# USB.net
KiCad netlist of a schematic drawn in Altium Designer
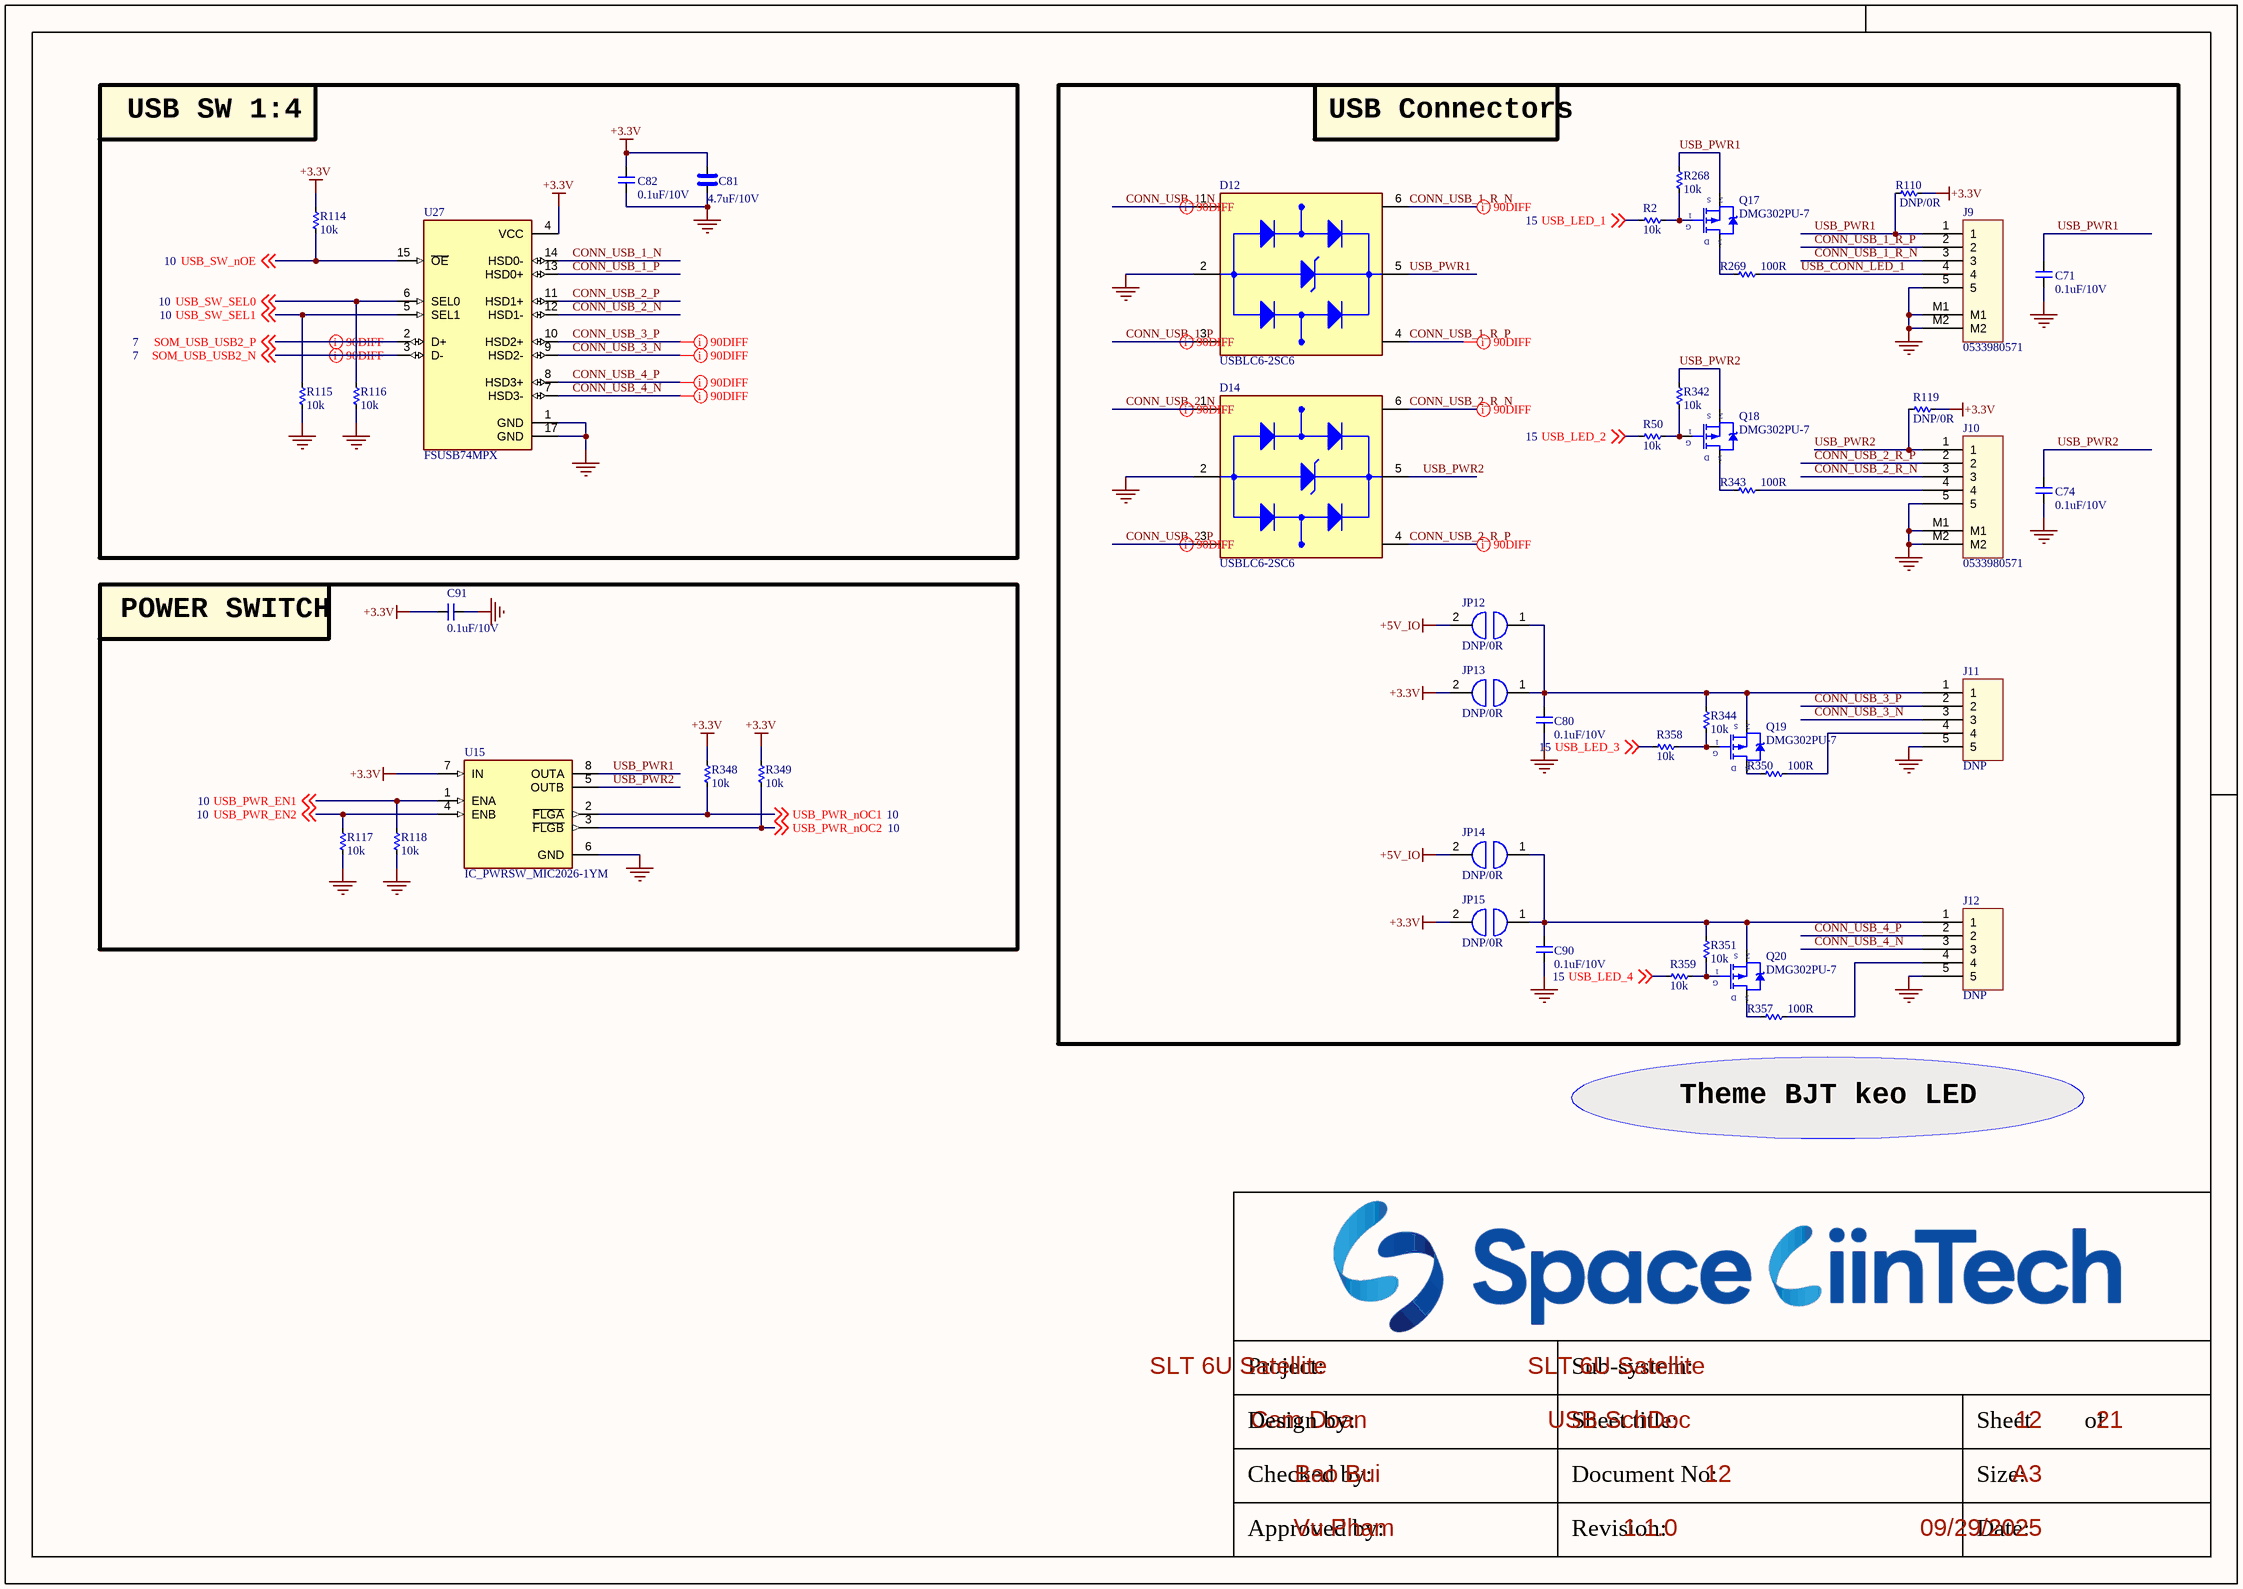
[diagram p0: USB.SchDoc]

(export (version "E")
  (design (tool "Eeschema 10.0.6"))
  (components
    (comp (ref "C71")
      (value "0.1uF/10V")
      (footprint "CAP_C_1005X60")
      (description "CAP CHIP")
      (libsource (lib "LABLIB") (part "_CAP_C_2"))
    )
    (comp (ref "C74")
      (value "0.1uF/10V")
      (footprint "CAP_C_1005X60")
      (description "CAP CHIP")
      (libsource (lib "LABLIB") (part "_CAP_C_2"))
    )
    (comp (ref "C80")
      (value "0.1uF/10V")
      (footprint "CAP_C_1005X60")
      (description "CAP CHIP")
      (libsource (lib "LABLIB") (part "_CAP_C_2"))
    )
    (comp (ref "C81")
      (value "4.7uF/10V")
      (footprint "CAP_C_1608X80")
      (description "CAP CHIP High Value")
      (libsource (lib "LABLIB") (part "_CAP_C_High_2"))
    )
    (comp (ref "C82")
      (value "0.1uF/10V")
      (footprint "CAP_C_1005X60")
      (description "CAP CHIP")
      (libsource (lib "LABLIB") (part "_CAP_C_2"))
    )
    (comp (ref "C90")
      (value "0.1uF/10V")
      (footprint "CAP_C_1005X60")
      (description "CAP CHIP")
      (libsource (lib "LABLIB") (part "_CAP_C_2"))
    )
    (comp (ref "C91")
      (value "0.1uF/10V")
      (footprint "CAP_C_1005X60")
      (description "CAP CHIP")
      (libsource (lib "LABLIB") (part "_CAP_C_2"))
    )
    (comp (ref "D12")
      (value "USBLC6-2SC6")
      (footprint "SOT95P280X145-6N")
      (description "17V Clamp 5A (8/20Âµs) Ipp Tvs Diode Surface Mount SOT-23-6")
      (fields (field (name "MF") "STMicroelectronics"))
      (libsource (lib "USBLC6-2SC6") (part "USBLC6-2SC6"))
    )
    (comp (ref "D14")
      (value "USBLC6-2SC6")
      (footprint "SOT95P280X145-6N")
      (description "17V Clamp 5A (8/20Âµs) Ipp Tvs Diode Surface Mount SOT-23-6")
      (fields (field (name "MF") "STMicroelectronics"))
      (libsource (lib "USBLC6-2SC6") (part "USBLC6-2SC6"))
    )
    (comp (ref "J9")
      (value "0533980571")
      (footprint "MOLEX_0533980571")
      (libsource (lib "LABLIB") (part "Header 5x1_2M"))
    )
    (comp (ref "J10")
      (value "0533980571")
      (footprint "MOLEX_0533980571")
      (libsource (lib "LABLIB") (part "Header 5x1_2M"))
    )
    (comp (ref "J11") (value "DNP") (footprint "SMD_5_PIN") (libsource (lib "LABLIB") (part "Header 5x1")))
    (comp (ref "J12") (value "DNP") (footprint "SMD_5_PIN") (libsource (lib "LABLIB") (part "Header 5x1")))
    (comp (ref "JP12")
      (value "DNP/0R")
      (footprint "RES_C_1608X60")
      (libsource (lib "EXP_V1") (part "JUMPER"))
    )
    (comp (ref "JP13")
      (value "DNP/0R")
      (footprint "RES_C_1608X60")
      (libsource (lib "EXP_V1") (part "JUMPER"))
    )
    (comp (ref "JP14")
      (value "DNP/0R")
      (footprint "RES_C_1608X60")
      (libsource (lib "EXP_V1") (part "JUMPER"))
    )
    (comp (ref "JP15")
      (value "DNP/0R")
      (footprint "RES_C_1608X60")
      (libsource (lib "EXP_V1") (part "JUMPER"))
    )
    (comp (ref "Q17")
      (value "DMG302PU-7")
      (footprint "SOT95P240X120-3N")
      (libsource (lib "LABLIB") (part "MOSFET_P_GSD"))
    )
    (comp (ref "Q18")
      (value "DMG302PU-7")
      (footprint "SOT95P240X120-3N")
      (libsource (lib "LABLIB") (part "MOSFET_P_GSD"))
    )
    (comp (ref "Q19")
      (value "DMG302PU-7")
      (footprint "SOT95P240X120-3N")
      (libsource (lib "LABLIB") (part "MOSFET_P_GSD"))
    )
    (comp (ref "Q20")
      (value "DMG302PU-7")
      (footprint "SOT95P240X120-3N")
      (libsource (lib "LABLIB") (part "MOSFET_P_GSD"))
    )
    (comp (ref "R2")
      (value "10k")
      (footprint "RES_C_1005X40")
      (description "RES")
      (libsource (lib "LABLIB") (part "_RES_B_2"))
    )
    (comp (ref "R50")
      (value "10k")
      (footprint "RES_C_1005X40")
      (description "RES")
      (libsource (lib "LABLIB") (part "_RES_B_2"))
    )
    (comp (ref "R110")
      (value "DNP/0R")
      (footprint "RES_C_1005X40")
      (description "RES")
      (libsource (lib "LABLIB") (part "_RES_B_2"))
    )
    (comp (ref "R114")
      (value "10k")
      (footprint "RES_C_1005X40")
      (description "RES")
      (libsource (lib "LABLIB") (part "_RES_B_2"))
    )
    (comp (ref "R115")
      (value "10k")
      (footprint "RES_C_1005X40")
      (description "RES")
      (libsource (lib "LABLIB") (part "_RES_B_2"))
    )
    (comp (ref "R116")
      (value "10k")
      (footprint "RES_C_1005X40")
      (description "RES")
      (libsource (lib "LABLIB") (part "_RES_B_2"))
    )
    (comp (ref "R117")
      (value "10k")
      (footprint "RES_C_1005X40")
      (description "RES")
      (libsource (lib "LABLIB") (part "_RES_B_2"))
    )
    (comp (ref "R118")
      (value "10k")
      (footprint "RES_C_1005X40")
      (description "RES")
      (libsource (lib "LABLIB") (part "_RES_B_2"))
    )
    (comp (ref "R119")
      (value "DNP/0R")
      (footprint "RES_C_1005X40")
      (description "RES")
      (libsource (lib "LABLIB") (part "_RES_B_2"))
    )
    (comp (ref "R268")
      (value "10k")
      (footprint "RES_C_1005X40")
      (description "RES")
      (libsource (lib "LABLIB") (part "_RES_B_2"))
    )
    (comp (ref "R269")
      (value "100R")
      (footprint "RES_C_1005X40")
      (description "RES")
      (libsource (lib "LABLIB") (part "_RES_B_2"))
    )
    (comp (ref "R342")
      (value "10k")
      (footprint "RES_C_1005X40")
      (description "RES")
      (libsource (lib "LABLIB") (part "_RES_B_2"))
    )
    (comp (ref "R343")
      (value "100R")
      (footprint "RES_C_1005X40")
      (description "RES")
      (libsource (lib "LABLIB") (part "_RES_B_2"))
    )
    (comp (ref "R344")
      (value "10k")
      (footprint "RES_C_1005X40")
      (description "RES")
      (libsource (lib "LABLIB") (part "_RES_B_2"))
    )
    (comp (ref "R348")
      (value "10k")
      (footprint "RES_C_1005X40")
      (description "RES")
      (libsource (lib "LABLIB") (part "_RES_B_2"))
    )
    (comp (ref "R349")
      (value "10k")
      (footprint "RES_C_1005X40")
      (description "RES")
      (libsource (lib "LABLIB") (part "_RES_B_2"))
    )
    (comp (ref "R350")
      (value "100R")
      (footprint "RES_C_1005X40")
      (description "RES")
      (libsource (lib "LABLIB") (part "_RES_B_2"))
    )
    (comp (ref "R351")
      (value "10k")
      (footprint "RES_C_1005X40")
      (description "RES")
      (libsource (lib "LABLIB") (part "_RES_B_2"))
    )
    (comp (ref "R357")
      (value "100R")
      (footprint "RES_C_1005X40")
      (description "RES")
      (libsource (lib "LABLIB") (part "_RES_B_2"))
    )
    (comp (ref "R358")
      (value "10k")
      (footprint "RES_C_1005X40")
      (description "RES")
      (libsource (lib "LABLIB") (part "_RES_B_2"))
    )
    (comp (ref "R359")
      (value "10k")
      (footprint "RES_C_1005X40")
      (description "RES")
      (libsource (lib "LABLIB") (part "_RES_B_2"))
    )
    (comp (ref "U15")
      (value "IC_PWRSW_MIC2026-1YM")
      (footprint "SOIC127P602X173-8N")
      (description "Power Switch/Driver 1:2 N-Channel 1.25A 8-SOIC")
      (fields (field (name "MF") "Microchip") (field (name "MP") "MIC2026-1YM"))
      (libsource (lib "LABLIB") (part "IC_PWRSW_MIC2026-1YM"))
    )
    (comp (ref "U27")
      (value "FSUSB74MPX")
      (footprint "QFN50P300X300X80-17N")
      (description "USB Switch IC 1 Channel 16-MLP (3x3)")
      (fields (field (name "MF") "ON Semiconductor"))
      (libsource (lib "LABLIB") (part "IC_USB_SW_FSUSB74MPX"))
    )
  )
  (nets
    (net (code "1") (name "+3.3V") (class "Default")
      (node (ref "C81") (pin "2") (pinfunction "2_2") (pintype "passive"))
      (node (ref "C82") (pin "2") (pinfunction "2_2") (pintype "passive"))
      (node (ref "C91") (pin "2") (pinfunction "2_2") (pintype "passive"))
      (node (ref "JP13") (pin "2") (pinfunction "2_2") (pintype "passive"))
      (node (ref "JP15") (pin "2") (pinfunction "2_2") (pintype "passive"))
      (node (ref "R110") (pin "1") (pinfunction "1_1") (pintype "passive"))
      (node (ref "R114") (pin "1") (pinfunction "1_1") (pintype "passive"))
      (node (ref "R119") (pin "1") (pinfunction "1_1") (pintype "passive"))
      (node (ref "R348") (pin "1") (pinfunction "1_1") (pintype "passive"))
      (node (ref "R349") (pin "1") (pinfunction "1_1") (pintype "passive"))
      (node (ref "U15") (pin "7") (pinfunction "IN_7") (pintype "input"))
      (node (ref "U27") (pin "4") (pinfunction "VCC_4") (pintype "power_in"))
    )
    (net (code "2") (name "+5V_IO") (class "Default")
      (node (ref "JP12") (pin "2") (pinfunction "2_2") (pintype "passive"))
      (node (ref "JP14") (pin "2") (pinfunction "2_2") (pintype "passive"))
    )
    (net (code "3") (name "/CONN_USB_1_N") (class "Default")
      (node (ref "D12") (pin "1") (pinfunction "I/O1_IN_1") (pintype "passive"))
      (node (ref "U27") (pin "14") (pinfunction "HSD0-_14") (pintype "bidirectional"))
    )
    (net (code "4") (name "/CONN_USB_1_P") (class "Default")
      (node (ref "D12") (pin "3") (pinfunction "I/O2_IN_3") (pintype "passive"))
      (node (ref "U27") (pin "13") (pinfunction "HSD0+_13") (pintype "bidirectional"))
    )
    (net (code "5") (name "/CONN_USB_1_R_N") (class "Default")
      (node (ref "D12") (pin "6") (pinfunction "I/O1_OUT_6") (pintype "passive"))
      (node (ref "J9") (pin "3") (pinfunction "3_3") (pintype "passive"))
    )
    (net (code "6") (name "/CONN_USB_1_R_P") (class "Default")
      (node (ref "D12") (pin "4") (pinfunction "I/O2_OUT_4") (pintype "passive"))
      (node (ref "J9") (pin "2") (pinfunction "2_2") (pintype "passive"))
    )
    (net (code "7") (name "/CONN_USB_2_N") (class "Default")
      (node (ref "D14") (pin "1") (pinfunction "I/O1_IN_1") (pintype "passive"))
      (node (ref "U27") (pin "12") (pinfunction "HSD1-_12") (pintype "bidirectional"))
    )
    (net (code "8") (name "/CONN_USB_2_P") (class "Default")
      (node (ref "D14") (pin "3") (pinfunction "I/O2_IN_3") (pintype "passive"))
      (node (ref "U27") (pin "11") (pinfunction "HSD1+_11") (pintype "bidirectional"))
    )
    (net (code "9") (name "/CONN_USB_2_R_N") (class "Default")
      (node (ref "D14") (pin "6") (pinfunction "I/O1_OUT_6") (pintype "passive"))
      (node (ref "J10") (pin "3") (pinfunction "3_3") (pintype "passive"))
    )
    (net (code "10") (name "/CONN_USB_2_R_P") (class "Default")
      (node (ref "D14") (pin "4") (pinfunction "I/O2_OUT_4") (pintype "passive"))
      (node (ref "J10") (pin "2") (pinfunction "2_2") (pintype "passive"))
    )
    (net (code "11") (name "/CONN_USB_3_N") (class "Default")
      (node (ref "J11") (pin "3") (pinfunction "3_3") (pintype "passive"))
      (node (ref "U27") (pin "9") (pinfunction "HSD2-_9") (pintype "bidirectional"))
    )
    (net (code "12") (name "/CONN_USB_3_P") (class "Default")
      (node (ref "J11") (pin "2") (pinfunction "2_2") (pintype "passive"))
      (node (ref "U27") (pin "10") (pinfunction "HSD2+_10") (pintype "bidirectional"))
    )
    (net (code "13") (name "/CONN_USB_4_N") (class "Default")
      (node (ref "J12") (pin "3") (pinfunction "3_3") (pintype "passive"))
      (node (ref "U27") (pin "7") (pinfunction "HSD3-_7") (pintype "bidirectional"))
    )
    (net (code "14") (name "/CONN_USB_4_P") (class "Default")
      (node (ref "J12") (pin "2") (pinfunction "2_2") (pintype "passive"))
      (node (ref "U27") (pin "8") (pinfunction "HSD3+_8") (pintype "bidirectional"))
    )
    (net (code "15") (name "/USB_CONN_LED_1") (class "Default")
      (node (ref "J9") (pin "4") (pinfunction "4_4") (pintype "passive"))
      (node (ref "R269") (pin "2") (pinfunction "2_2") (pintype "passive"))
    )
    (net (code "16") (name "/USB_PWR1") (class "Default")
      (node (ref "C71") (pin "2") (pinfunction "2_2") (pintype "passive"))
      (node (ref "D12") (pin "5") (pinfunction "VBUS_5") (pintype "power_in"))
      (node (ref "J9") (pin "1") (pinfunction "1_1") (pintype "passive"))
      (node (ref "Q17") (pin "2") (pinfunction "S_2") (pintype "passive"))
      (node (ref "R110") (pin "2") (pinfunction "2_2") (pintype "passive"))
      (node (ref "R268") (pin "1") (pinfunction "1_1") (pintype "passive"))
      (node (ref "U15") (pin "8") (pinfunction "OUTA_8") (pintype "passive"))
    )
    (net (code "17") (name "/USB_PWR2") (class "Default")
      (node (ref "C74") (pin "2") (pinfunction "2_2") (pintype "passive"))
      (node (ref "D14") (pin "5") (pinfunction "VBUS_5") (pintype "power_in"))
      (node (ref "J10") (pin "1") (pinfunction "1_1") (pintype "passive"))
      (node (ref "Q18") (pin "2") (pinfunction "S_2") (pintype "passive"))
      (node (ref "R119") (pin "2") (pinfunction "2_2") (pintype "passive"))
      (node (ref "R342") (pin "1") (pinfunction "1_1") (pintype "passive"))
      (node (ref "U15") (pin "5") (pinfunction "OUTB_5") (pintype "passive"))
    )
    (net (code "18") (name "GND") (class "Default")
      (node (ref "C71") (pin "1") (pinfunction "1_1") (pintype "passive"))
      (node (ref "C74") (pin "1") (pinfunction "1_1") (pintype "passive"))
      (node (ref "C80") (pin "1") (pinfunction "1_1") (pintype "passive"))
      (node (ref "C81") (pin "1") (pinfunction "1_1") (pintype "passive"))
      (node (ref "C82") (pin "1") (pinfunction "1_1") (pintype "passive"))
      (node (ref "C90") (pin "1") (pinfunction "1_1") (pintype "passive"))
      (node (ref "C91") (pin "1") (pinfunction "1_1") (pintype "passive"))
      (node (ref "D12") (pin "2") (pinfunction "GND_2") (pintype "power_in"))
      (node (ref "D14") (pin "2") (pinfunction "GND_2") (pintype "power_in"))
      (node (ref "J10") (pin "5") (pinfunction "5_5") (pintype "passive"))
      (node (ref "J10") (pin "M1") (pinfunction "M1_M1") (pintype "passive"))
      (node (ref "J10") (pin "M2") (pinfunction "M2_M2") (pintype "passive"))
      (node (ref "J11") (pin "5") (pinfunction "5_5") (pintype "passive"))
      (node (ref "J12") (pin "5") (pinfunction "5_5") (pintype "passive"))
      (node (ref "J9") (pin "5") (pinfunction "5_5") (pintype "passive"))
      (node (ref "J9") (pin "M1") (pinfunction "M1_M1") (pintype "passive"))
      (node (ref "J9") (pin "M2") (pinfunction "M2_M2") (pintype "passive"))
      (node (ref "R115") (pin "2") (pinfunction "2_2") (pintype "passive"))
      (node (ref "R116") (pin "2") (pinfunction "2_2") (pintype "passive"))
      (node (ref "R117") (pin "2") (pinfunction "2_2") (pintype "passive"))
      (node (ref "R118") (pin "2") (pinfunction "2_2") (pintype "passive"))
      (node (ref "U15") (pin "6") (pinfunction "GND_6") (pintype "power_in"))
      (node (ref "U27") (pin "1") (pinfunction "GND_1") (pintype "power_in"))
      (node (ref "U27") (pin "17") (pinfunction "GND_17") (pintype "power_in"))
    )
    (net (code "19") (name "Net-(J10-Pad4)") (class "Default")
      (node (ref "J10") (pin "4") (pinfunction "4_4") (pintype "passive"))
      (node (ref "R343") (pin "2") (pinfunction "2_2") (pintype "passive"))
    )
    (net (code "20") (name "Net-(J11-Pad4)") (class "Default")
      (node (ref "J11") (pin "4") (pinfunction "4_4") (pintype "passive"))
      (node (ref "R350") (pin "2") (pinfunction "2_2") (pintype "passive"))
    )
    (net (code "21") (name "Net-(J12-Pad4)") (class "Default")
      (node (ref "J12") (pin "4") (pinfunction "4_4") (pintype "passive"))
      (node (ref "R357") (pin "2") (pinfunction "2_2") (pintype "passive"))
    )
    (net (code "22") (name "Net-(Q17-D)") (class "Default")
      (node (ref "Q17") (pin "3") (pinfunction "D_3") (pintype "passive"))
      (node (ref "R269") (pin "1") (pinfunction "1_1") (pintype "passive"))
    )
    (net (code "23") (name "Net-(Q17-G)") (class "Default")
      (node (ref "Q17") (pin "1") (pinfunction "G_1") (pintype "passive"))
      (node (ref "R2") (pin "2") (pinfunction "2_2") (pintype "passive"))
      (node (ref "R268") (pin "2") (pinfunction "2_2") (pintype "passive"))
    )
    (net (code "24") (name "Net-(Q18-D)") (class "Default")
      (node (ref "Q18") (pin "3") (pinfunction "D_3") (pintype "passive"))
      (node (ref "R343") (pin "1") (pinfunction "1_1") (pintype "passive"))
    )
    (net (code "25") (name "Net-(Q18-G)") (class "Default")
      (node (ref "Q18") (pin "1") (pinfunction "G_1") (pintype "passive"))
      (node (ref "R342") (pin "2") (pinfunction "2_2") (pintype "passive"))
      (node (ref "R50") (pin "2") (pinfunction "2_2") (pintype "passive"))
    )
    (net (code "26") (name "Net-(Q19-D)") (class "Default")
      (node (ref "Q19") (pin "3") (pinfunction "D_3") (pintype "passive"))
      (node (ref "R350") (pin "1") (pinfunction "1_1") (pintype "passive"))
    )
    (net (code "27") (name "Net-(Q19-G)") (class "Default")
      (node (ref "Q19") (pin "1") (pinfunction "G_1") (pintype "passive"))
      (node (ref "R344") (pin "2") (pinfunction "2_2") (pintype "passive"))
      (node (ref "R358") (pin "2") (pinfunction "2_2") (pintype "passive"))
    )
    (net (code "28") (name "Net-(Q19-S)") (class "Default")
      (node (ref "C80") (pin "2") (pinfunction "2_2") (pintype "passive"))
      (node (ref "J11") (pin "1") (pinfunction "1_1") (pintype "passive"))
      (node (ref "JP12") (pin "1") (pinfunction "1_1") (pintype "passive"))
      (node (ref "JP13") (pin "1") (pinfunction "1_1") (pintype "passive"))
      (node (ref "Q19") (pin "2") (pinfunction "S_2") (pintype "passive"))
      (node (ref "R344") (pin "1") (pinfunction "1_1") (pintype "passive"))
    )
    (net (code "29") (name "Net-(Q20-D)") (class "Default")
      (node (ref "Q20") (pin "3") (pinfunction "D_3") (pintype "passive"))
      (node (ref "R357") (pin "1") (pinfunction "1_1") (pintype "passive"))
    )
    (net (code "30") (name "Net-(Q20-G)") (class "Default")
      (node (ref "Q20") (pin "1") (pinfunction "G_1") (pintype "passive"))
      (node (ref "R351") (pin "2") (pinfunction "2_2") (pintype "passive"))
      (node (ref "R359") (pin "2") (pinfunction "2_2") (pintype "passive"))
    )
    (net (code "31") (name "Net-(Q20-S)") (class "Default")
      (node (ref "C90") (pin "2") (pinfunction "2_2") (pintype "passive"))
      (node (ref "J12") (pin "1") (pinfunction "1_1") (pintype "passive"))
      (node (ref "JP14") (pin "1") (pinfunction "1_1") (pintype "passive"))
      (node (ref "JP15") (pin "1") (pinfunction "1_1") (pintype "passive"))
      (node (ref "Q20") (pin "2") (pinfunction "S_2") (pintype "passive"))
      (node (ref "R351") (pin "1") (pinfunction "1_1") (pintype "passive"))
    )
    (net (code "32") (name "SOM_USB_USB2_N") (class "Default")
      (node (ref "U27") (pin "3") (pinfunction "D-_3") (pintype "bidirectional"))
    )
    (net (code "33") (name "SOM_USB_USB2_P") (class "Default")
      (node (ref "U27") (pin "2") (pinfunction "D+_2") (pintype "bidirectional"))
    )
    (net (code "34") (name "USB_LED_1") (class "Default")
      (node (ref "R2") (pin "1") (pinfunction "1_1") (pintype "passive"))
    )
    (net (code "35") (name "USB_LED_2") (class "Default")
      (node (ref "R50") (pin "1") (pinfunction "1_1") (pintype "passive"))
    )
    (net (code "36") (name "USB_LED_3") (class "Default")
      (node (ref "R358") (pin "1") (pinfunction "1_1") (pintype "passive"))
    )
    (net (code "37") (name "USB_LED_4") (class "Default")
      (node (ref "R359") (pin "1") (pinfunction "1_1") (pintype "passive"))
    )
    (net (code "38") (name "USB_PWR_EN1") (class "Default")
      (node (ref "R118") (pin "1") (pinfunction "1_1") (pintype "passive"))
      (node (ref "U15") (pin "1") (pinfunction "ENA_1") (pintype "input"))
    )
    (net (code "39") (name "USB_PWR_EN2") (class "Default")
      (node (ref "R117") (pin "1") (pinfunction "1_1") (pintype "passive"))
      (node (ref "U15") (pin "4") (pinfunction "ENB_4") (pintype "input"))
    )
    (net (code "40") (name "USB_PWR_nOC1") (class "Default")
      (node (ref "R348") (pin "2") (pinfunction "2_2") (pintype "passive"))
      (node (ref "U15") (pin "2") (pinfunction "~{FLGA}_2") (pintype "output"))
    )
    (net (code "41") (name "USB_PWR_nOC2") (class "Default")
      (node (ref "R349") (pin "2") (pinfunction "2_2") (pintype "passive"))
      (node (ref "U15") (pin "3") (pinfunction "~{FLGB}_3") (pintype "output"))
    )
    (net (code "42") (name "USB_SW_SEL0") (class "Default")
      (node (ref "R116") (pin "1") (pinfunction "1_1") (pintype "passive"))
      (node (ref "U27") (pin "6") (pinfunction "SEL0_6") (pintype "input"))
    )
    (net (code "43") (name "USB_SW_SEL1") (class "Default")
      (node (ref "R115") (pin "1") (pinfunction "1_1") (pintype "passive"))
      (node (ref "U27") (pin "5") (pinfunction "SEL1_5") (pintype "input"))
    )
    (net (code "44") (name "USB_SW_nOE") (class "Default")
      (node (ref "R114") (pin "2") (pinfunction "2_2") (pintype "passive"))
      (node (ref "U27") (pin "15") (pinfunction "~{OE}_15") (pintype "input"))
    )
  )
)
